# Sensors.net
KiCad netlist of a schematic drawn in Altium Designer
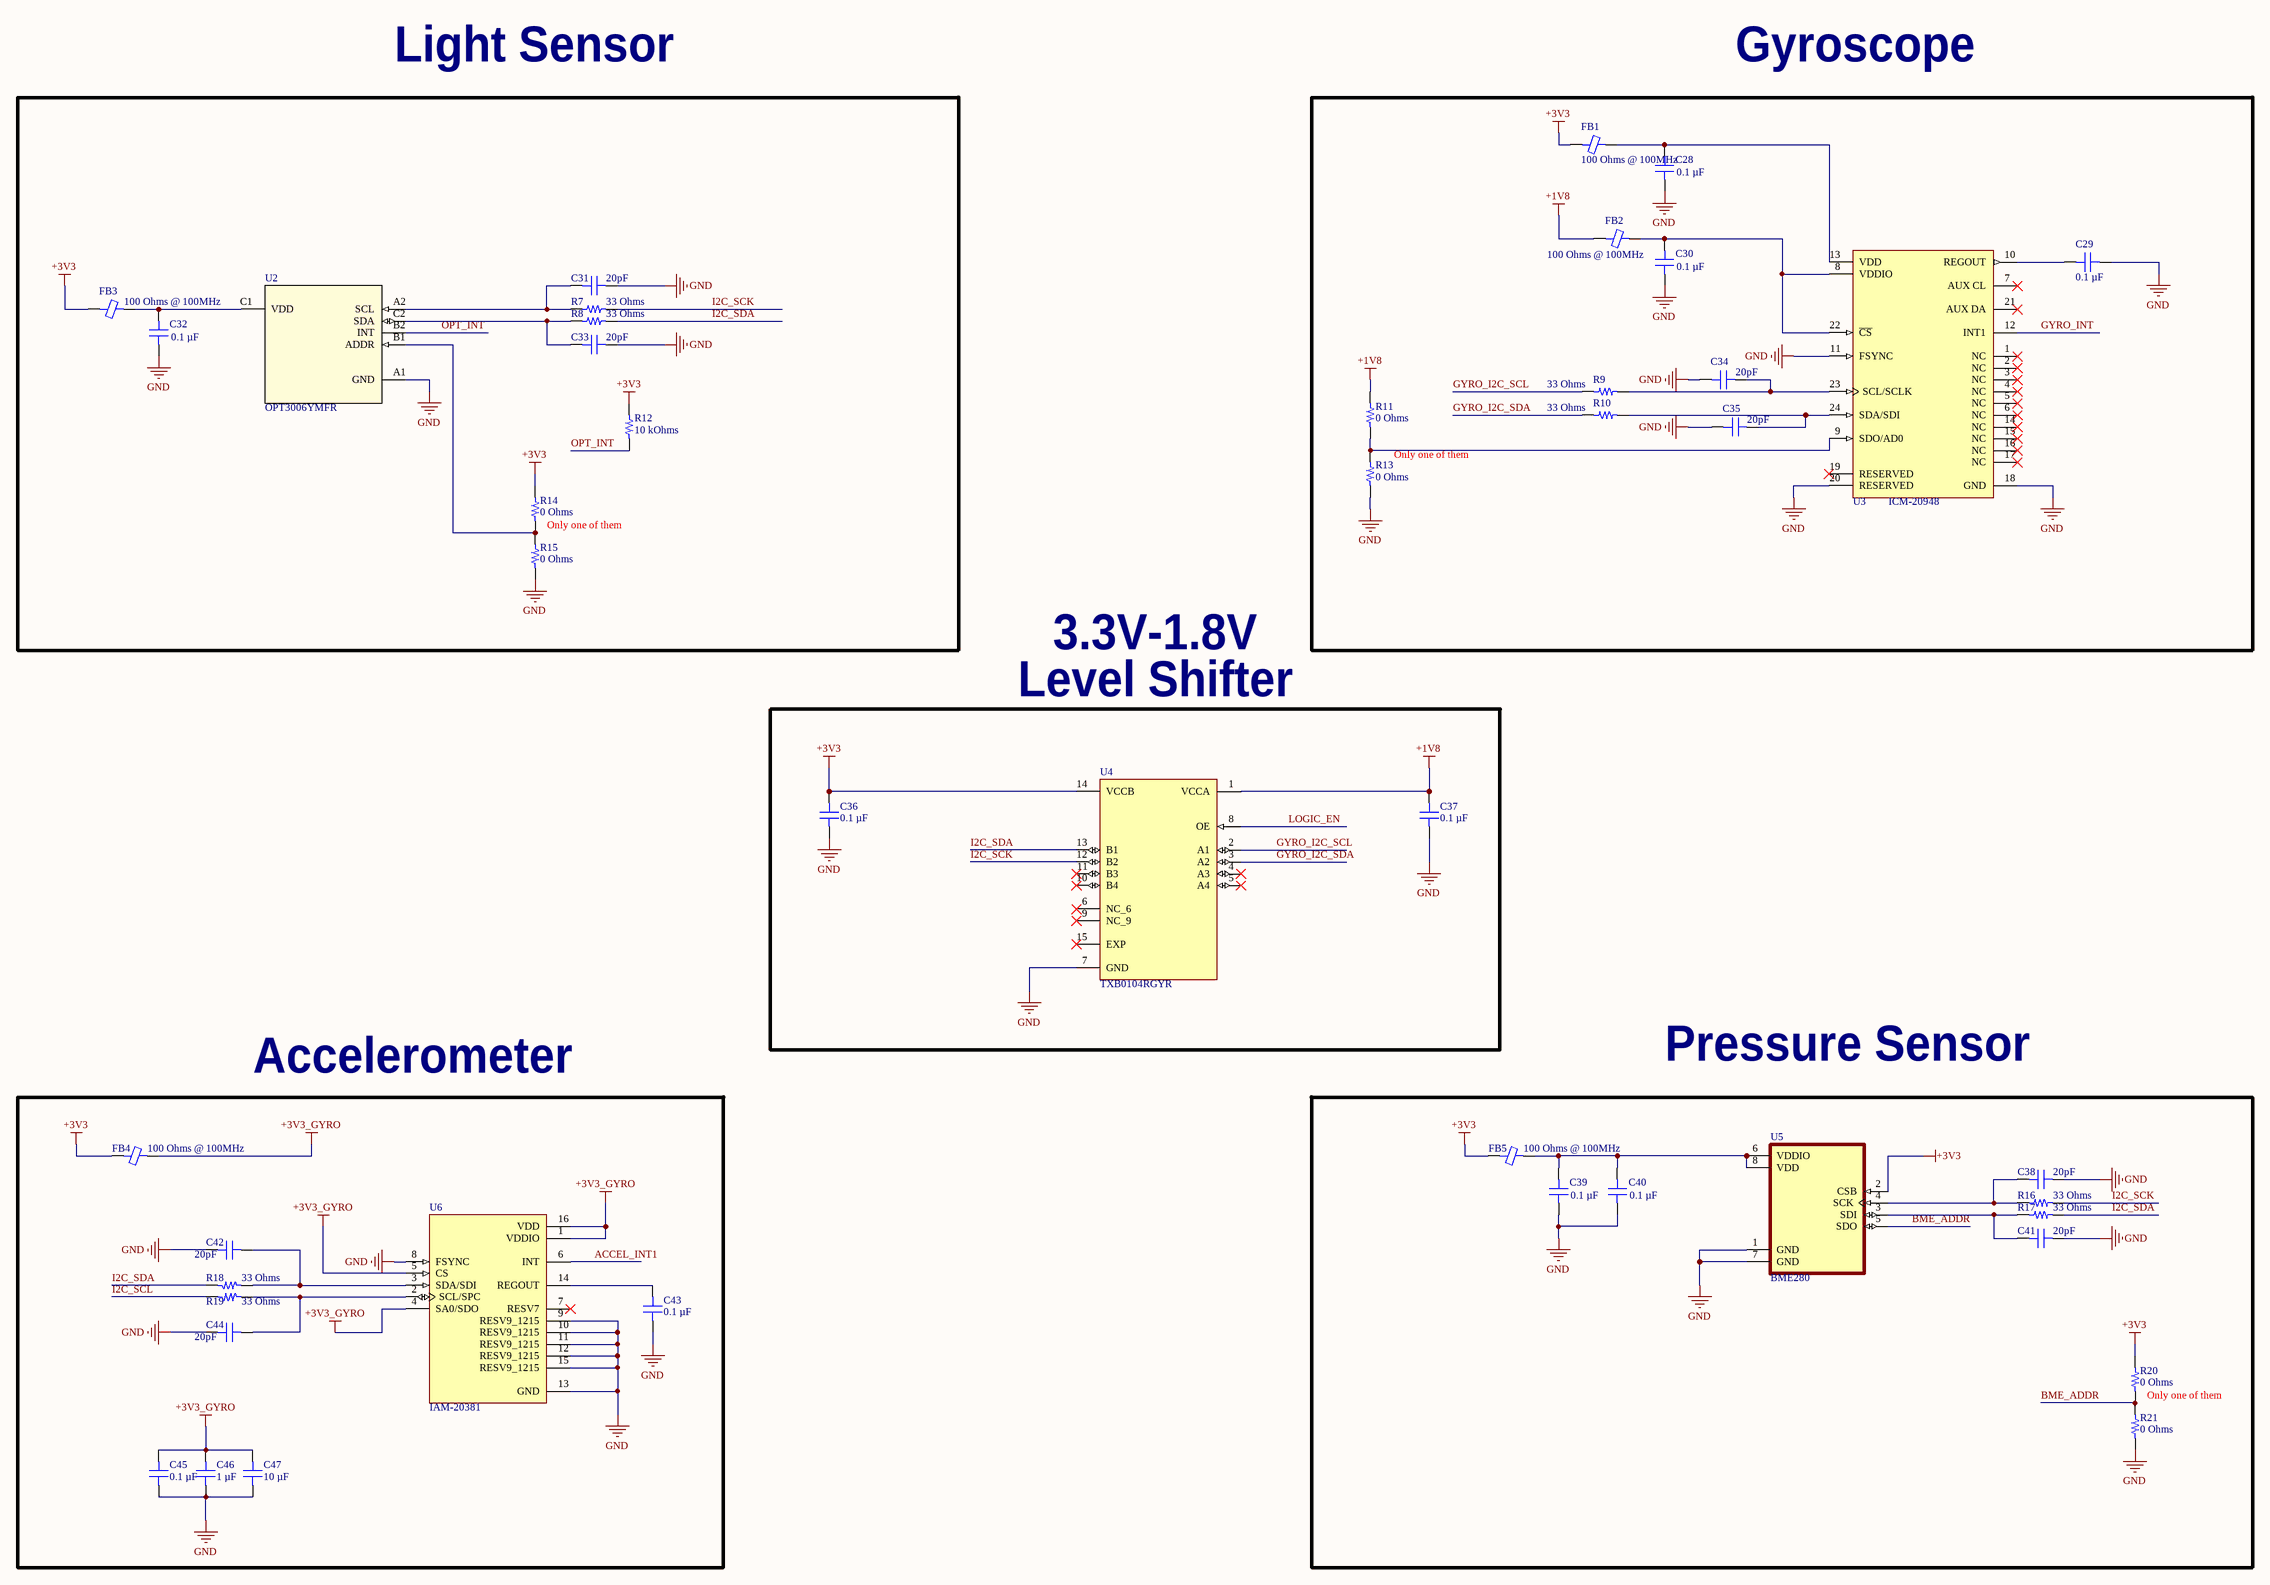
[diagram p0: Sensors.SchDoc]

(export (version "E")
  (design (tool "Eeschema 10.0.6"))
  (components
    (comp (ref "C28")
      (value "0.1 µF")
      (footprint "CAP 0603_1608")
      (description "CAP CER 0.1UF 16V X7R 0603")
      (fields (field (name "PART NUMBER") "CS0603KRX7R7BB104") (field (name "MANUFACTURER") "Yageo"))
      (libsource (lib "Celestial Altium Library - altium_library") (part "Capacitor"))
    )
    (comp (ref "C29")
      (value "0.1 µF")
      (footprint "CAP 0603_1608")
      (description "CAP CER 0.1UF 16V X7R 0603")
      (fields (field (name "PART NUMBER") "CS0603KRX7R7BB104") (field (name "MANUFACTURER") "Yageo"))
      (libsource (lib "Celestial Altium Library - altium_library") (part "Capacitor"))
    )
    (comp (ref "C30")
      (value "0.1 µF")
      (footprint "CAP 0603_1608")
      (description "CAP CER 0.1UF 16V X7R 0603")
      (fields (field (name "PART NUMBER") "CS0603KRX7R7BB104") (field (name "MANUFACTURER") "Yageo"))
      (libsource (lib "Celestial Altium Library - altium_library") (part "Capacitor"))
    )
    (comp (ref "C31")
      (value "20pF")
      (footprint "CAP 0603_1608")
      (description "CAP CER 20PF 25V C0G/NP0 0603")
      (fields (field (name "PART NUMBER") "06033A200JAT2A") (field (name "MANUFACTURER") "AVX Corporation"))
      (libsource (lib "Celestial Altium Library - altium_library") (part "Capacitor"))
    )
    (comp (ref "C32")
      (value "0.1 µF")
      (footprint "CAP 0603_1608")
      (description "CAP CER 0.1UF 16V X7R 0603")
      (fields (field (name "PART NUMBER") "CS0603KRX7R7BB104") (field (name "MANUFACTURER") "Yageo"))
      (libsource (lib "Celestial Altium Library - altium_library") (part "Capacitor"))
    )
    (comp (ref "C33")
      (value "20pF")
      (footprint "CAP 0603_1608")
      (description "CAP CER 20PF 25V C0G/NP0 0603")
      (fields (field (name "PART NUMBER") "06033A200JAT2A") (field (name "MANUFACTURER") "AVX Corporation"))
      (libsource (lib "Celestial Altium Library - altium_library") (part "Capacitor"))
    )
    (comp (ref "C34")
      (value "20pF")
      (footprint "CAP 0603_1608")
      (description "CAP CER 20PF 25V C0G/NP0 0603")
      (fields (field (name "PART NUMBER") "06033A200JAT2A") (field (name "MANUFACTURER") "AVX Corporation"))
      (libsource (lib "Celestial Altium Library - altium_library") (part "Capacitor"))
    )
    (comp (ref "C35")
      (value "20pF")
      (footprint "CAP 0603_1608")
      (description "CAP CER 20PF 25V C0G/NP0 0603")
      (fields (field (name "PART NUMBER") "06033A200JAT2A") (field (name "MANUFACTURER") "AVX Corporation"))
      (libsource (lib "Celestial Altium Library - altium_library") (part "Capacitor"))
    )
    (comp (ref "C36")
      (value "0.1 µF")
      (footprint "CAP 0603_1608")
      (description "CAP CER 0.1UF 25V X5R 0603")
      (fields (field (name "PART NUMBER") "TMK107BJ104KA-T") (field (name "MANUFACTURER") "Taiyo Yuden"))
      (libsource (lib "Celestial Altium Library - altium_library") (part "Capacitor"))
    )
    (comp (ref "C37")
      (value "0.1 µF")
      (footprint "CAP 0603_1608")
      (description "CAP CER 0.1UF 25V X5R 0603")
      (fields (field (name "PART NUMBER") "TMK107BJ104KA-T") (field (name "MANUFACTURER") "Taiyo Yuden"))
      (libsource (lib "Celestial Altium Library - altium_library") (part "Capacitor"))
    )
    (comp (ref "C38")
      (value "20pF")
      (footprint "CAP 0603_1608")
      (description "CAP CER 20PF 25V C0G/NP0 0603")
      (fields (field (name "PART NUMBER") "06033A200JAT2A") (field (name "MANUFACTURER") "AVX Corporation"))
      (libsource (lib "Celestial Altium Library - altium_library") (part "Capacitor"))
    )
    (comp (ref "C39")
      (value "0.1 µF")
      (footprint "CAP 0603_1608")
      (description "CAP CER 0.1UF 16V X7R 0603")
      (fields (field (name "PART NUMBER") "CS0603KRX7R7BB104") (field (name "MANUFACTURER") "Yageo"))
      (libsource (lib "Celestial Altium Library - altium_library") (part "Capacitor"))
    )
    (comp (ref "C40")
      (value "0.1 µF")
      (footprint "CAP 0603_1608")
      (description "CAP CER 0.1UF 16V X7R 0603")
      (fields (field (name "PART NUMBER") "CS0603KRX7R7BB104") (field (name "MANUFACTURER") "Yageo"))
      (libsource (lib "Celestial Altium Library - altium_library") (part "Capacitor"))
    )
    (comp (ref "C41")
      (value "20pF")
      (footprint "CAP 0603_1608")
      (description "CAP CER 20PF 25V C0G/NP0 0603")
      (fields (field (name "PART NUMBER") "06033A200JAT2A") (field (name "MANUFACTURER") "AVX Corporation"))
      (libsource (lib "Celestial Altium Library - altium_library") (part "Capacitor"))
    )
    (comp (ref "C42")
      (value "20pF")
      (footprint "CAP 0603_1608")
      (description "CAP CER 20PF 25V C0G/NP0 0603")
      (fields (field (name "PART NUMBER") "06033A200JAT2A") (field (name "MANUFACTURER") "AVX Corporation"))
      (libsource (lib "Celestial Altium Library - altium_library") (part "Capacitor"))
    )
    (comp (ref "C43")
      (value "0.1 µF")
      (footprint "CAP 0603_1608")
      (description "CAP CER 0.1UF 25V X5R 0603")
      (fields (field (name "PART NUMBER") "TMK107BJ104KA-T") (field (name "MANUFACTURER") "Taiyo Yuden"))
      (libsource (lib "Celestial Altium Library - altium_library") (part "Capacitor"))
    )
    (comp (ref "C44")
      (value "20pF")
      (footprint "CAP 0603_1608")
      (description "CAP CER 20PF 25V C0G/NP0 0603")
      (fields (field (name "PART NUMBER") "06033A200JAT2A") (field (name "MANUFACTURER") "AVX Corporation"))
      (libsource (lib "Celestial Altium Library - altium_library") (part "Capacitor"))
    )
    (comp (ref "C45")
      (value "0.1 µF")
      (footprint "CAP 0603_1608")
      (description "CAP CER 0.1UF 25V X5R 0603")
      (fields (field (name "PART NUMBER") "TMK107BJ104KA-T") (field (name "MANUFACTURER") "Taiyo Yuden"))
      (libsource (lib "Celestial Altium Library - altium_library") (part "Capacitor"))
    )
    (comp (ref "C46")
      (value "1 µF")
      (footprint "CAP 0603_1608")
      (description "CAP CER 1UF 25V X5R 0603")
      (fields (field (name "PART NUMBER") "TMK107BJ105MAHT") (field (name "MANUFACTURER") "Taiyo Yuden"))
      (libsource (lib "Celestial Altium Library - altium_library") (part "Capacitor"))
    )
    (comp (ref "C47")
      (value "10 µF")
      (footprint "CAP 0603_1608")
      (description "CAP CER 10UF 25V X5R 0603")
      (fields (field (name "PART NUMBER") "TMK107BBJ106MA-T") (field (name "MANUFACTURER") "Taiyo Yuden"))
      (libsource (lib "Celestial Altium Library - altium_library") (part "Capacitor"))
    )
    (comp (ref "FB1")
      (value "100 Ohms @ 100MHz")
      (footprint "FER 0402_1005")
      (description "EMI BEAD FILETER")
      (fields
        (field (name "PART NUMBER") "BBSY00100505101Y00")
        (field (name "MANUFACTURER") "Chilisin Electronics")
      )
      (libsource (lib "Celestial Altium Library - altium_library") (part "Ferrite Chip"))
    )
    (comp (ref "FB2")
      (value "100 Ohms @ 100MHz")
      (footprint "FER 0402_1005")
      (description "EMI BEAD FILETER")
      (fields
        (field (name "PART NUMBER") "BBSY00100505101Y00")
        (field (name "MANUFACTURER") "Chilisin Electronics")
      )
      (libsource (lib "Celestial Altium Library - altium_library") (part "Ferrite Chip"))
    )
    (comp (ref "FB3")
      (value "100 Ohms @ 100MHz")
      (footprint "FER 0402_1005")
      (description "EMI BEAD FILETER")
      (fields
        (field (name "PART NUMBER") "BBSY00100505101Y00")
        (field (name "MANUFACTURER") "Chilisin Electronics")
      )
      (libsource (lib "Celestial Altium Library - altium_library") (part "Ferrite Chip"))
    )
    (comp (ref "FB4")
      (value "100 Ohms @ 100MHz")
      (footprint "FER 0402_1005")
      (description "EMI BEAD FILETER")
      (fields
        (field (name "PART NUMBER") "BBSY00100505101Y00")
        (field (name "MANUFACTURER") "Chilisin Electronics")
      )
      (libsource (lib "Celestial Altium Library - altium_library") (part "Ferrite Chip"))
    )
    (comp (ref "FB5")
      (value "100 Ohms @ 100MHz")
      (footprint "FER 0402_1005")
      (description "EMI BEAD FILETER")
      (fields
        (field (name "PART NUMBER") "BBSY00100505101Y00")
        (field (name "MANUFACTURER") "Chilisin Electronics")
      )
      (libsource (lib "Celestial Altium Library - altium_library") (part "Ferrite Chip"))
    )
    (comp (ref "R7")
      (value "33 Ohms")
      (footprint "RES 0603_1608")
      (description "RES SMD 33 OHM 1% 1/10W 0603")
      (fields (field (name "PART NUMBER") "AC0603FR-0733RL") (field (name "MANUFACTURER") "Yageo"))
      (libsource (lib "Celestial Altium Library - altium_library") (part "Resistor"))
    )
    (comp (ref "R8")
      (value "33 Ohms")
      (footprint "RES 0603_1608")
      (description "RES SMD 33 OHM 1% 1/10W 0603")
      (fields (field (name "PART NUMBER") "AC0603FR-0733RL") (field (name "MANUFACTURER") "Yageo"))
      (libsource (lib "Celestial Altium Library - altium_library") (part "Resistor"))
    )
    (comp (ref "R9")
      (value "33 Ohms")
      (footprint "RES 0603_1608")
      (description "RES SMD 33 OHM 1% 1/10W 0603")
      (fields (field (name "PART NUMBER") "AC0603FR-0733RL") (field (name "MANUFACTURER") "Yageo"))
      (libsource (lib "Celestial Altium Library - altium_library") (part "Resistor"))
    )
    (comp (ref "R10")
      (value "33 Ohms")
      (footprint "RES 0603_1608")
      (description "RES SMD 33 OHM 1% 1/10W 0603")
      (fields (field (name "PART NUMBER") "AC0603FR-0733RL") (field (name "MANUFACTURER") "Yageo"))
      (libsource (lib "Celestial Altium Library - altium_library") (part "Resistor"))
    )
    (comp (ref "R11")
      (value "0 Ohms")
      (footprint "RES 0603_1608")
      (description "RES SMD 0 OHM JUMPER 1/2W 0603")
      (fields (field (name "PART NUMBER") "5110") (field (name "MANUFACTURER") "Keystone Electronics"))
      (libsource (lib "Celestial Altium Library - altium_library") (part "Resistor"))
    )
    (comp (ref "R12")
      (value "10 kOhms")
      (footprint "RES 0603_1608")
      (description "RES SMD 10K OHM 5% 1/10W 0603")
      (fields (field (name "PART NUMBER") "AC0603JR-0710KL") (field (name "MANUFACTURER") "Yageo"))
      (libsource (lib "Celestial Altium Library - altium_library") (part "Resistor"))
    )
    (comp (ref "R13")
      (value "0 Ohms")
      (footprint "RES 0603_1608")
      (description "RES SMD 0 OHM JUMPER 1/2W 0603")
      (fields (field (name "PART NUMBER") "5110") (field (name "MANUFACTURER") "Keystone Electronics"))
      (libsource (lib "Celestial Altium Library - altium_library") (part "Resistor"))
    )
    (comp (ref "R14")
      (value "0 Ohms")
      (footprint "RES 0603_1608")
      (description "RES SMD 0 OHM JUMPER 1/2W 0603")
      (fields (field (name "PART NUMBER") "5110") (field (name "MANUFACTURER") "Keystone Electronics"))
      (libsource (lib "Celestial Altium Library - altium_library") (part "Resistor"))
    )
    (comp (ref "R15")
      (value "0 Ohms")
      (footprint "RES 0603_1608")
      (description "RES SMD 0 OHM JUMPER 1/2W 0603")
      (fields (field (name "PART NUMBER") "5110") (field (name "MANUFACTURER") "Keystone Electronics"))
      (libsource (lib "Celestial Altium Library - altium_library") (part "Resistor"))
    )
    (comp (ref "R16")
      (value "33 Ohms")
      (footprint "RES 0603_1608")
      (description "RES SMD 33 OHM 1% 1/10W 0603")
      (fields (field (name "PART NUMBER") "AC0603FR-0733RL") (field (name "MANUFACTURER") "Yageo"))
      (libsource (lib "Celestial Altium Library - altium_library") (part "Resistor"))
    )
    (comp (ref "R17")
      (value "33 Ohms")
      (footprint "RES 0603_1608")
      (description "RES SMD 33 OHM 1% 1/10W 0603")
      (fields (field (name "PART NUMBER") "AC0603FR-0733RL") (field (name "MANUFACTURER") "Yageo"))
      (libsource (lib "Celestial Altium Library - altium_library") (part "Resistor"))
    )
    (comp (ref "R18")
      (value "33 Ohms")
      (footprint "RES 0603_1608")
      (description "RES SMD 33 OHM 1% 1/10W 0603")
      (fields (field (name "PART NUMBER") "AC0603FR-0733RL") (field (name "MANUFACTURER") "Yageo"))
      (libsource (lib "Celestial Altium Library - altium_library") (part "Resistor"))
    )
    (comp (ref "R19")
      (value "33 Ohms")
      (footprint "RES 0603_1608")
      (description "RES SMD 33 OHM 1% 1/10W 0603")
      (fields (field (name "PART NUMBER") "AC0603FR-0733RL") (field (name "MANUFACTURER") "Yageo"))
      (libsource (lib "Celestial Altium Library - altium_library") (part "Resistor"))
    )
    (comp (ref "R20")
      (value "0 Ohms")
      (footprint "RES 0603_1608")
      (description "RES SMD 0 OHM JUMPER 1/2W 0603")
      (fields (field (name "PART NUMBER") "5110") (field (name "MANUFACTURER") "Keystone Electronics"))
      (libsource (lib "Celestial Altium Library - altium_library") (part "Resistor"))
    )
    (comp (ref "R21")
      (value "0 Ohms")
      (footprint "RES 0603_1608")
      (description "RES SMD 0 OHM JUMPER 1/2W 0603")
      (fields (field (name "PART NUMBER") "5110") (field (name "MANUFACTURER") "Keystone Electronics"))
      (libsource (lib "Celestial Altium Library - altium_library") (part "Resistor"))
    )
    (comp (ref "U2")
      (value "OPT3006YMFR")
      (footprint "YMF0006A")
      (description "No Description Available")
      (fields (field (name "COPYRIGHT") "Copyright (C) 2022 Ultra Librarian. All rights reserved."))
      (libsource (lib "OPT3006YMFR") (part "OPT3006YMFR"))
    )
    (comp (ref "U3")
      (value "ICM-20948")
      (footprint "TDK_InvenSense_0_IPC_C")
      (description "Accelerometer, Gyroscope, Magnetometer, 9 Axis Sensor I²C, SPI Output")
      (fields
        (field (name "DIGIKEY PART NUMBER") "1428-1123-1-ND")
        (field (name "MANUFACTURER") "TDK InvenSense")
      )
      (libsource (lib "EEConcierge") (part "ICM-20948"))
    )
    (comp (ref "U4")
      (value "TXB0104RGYR")
      (footprint "QFN50P350X350X100-15N")
      (libsource (lib "TXB0104RGYR") (part "TXB0104RGYR"))
    )
    (comp (ref "U5")
      (value "BME280")
      (footprint "PSON65P250X250X100-8N")
      (libsource (lib "BME280") (part "BME280"))
    )
    (comp (ref "U6")
      (value "IAM-20381")
      (footprint "PQFN50P300X300X80-16N")
      (description "Accelerometer X, Y, Z Axis Â±2g, 4g, 8g, 16g 16-LGA (3x3)")
      (fields (field (name "MF") "TDK InvenSense"))
      (libsource (lib "IAM-20381") (part "IAM-20381"))
    )
  )
  (nets
    (net (code "1") (name "+1V8") (class "Default")
      (node (ref "C37") (pin "2") (pinfunction "2_2") (pintype "passive"))
      (node (ref "FB2") (pin "1") (pinfunction "1_1") (pintype "passive"))
      (node (ref "R11") (pin "2") (pinfunction "2_2") (pintype "passive"))
      (node (ref "U4") (pin "1") (pinfunction "VCCA_1") (pintype "power_in"))
    )
    (net (code "2") (name "+3V3") (class "Default")
      (node (ref "C36") (pin "2") (pinfunction "2_2") (pintype "passive"))
      (node (ref "FB1") (pin "1") (pinfunction "1_1") (pintype "passive"))
      (node (ref "FB3") (pin "1") (pinfunction "1_1") (pintype "passive"))
      (node (ref "FB4") (pin "1") (pinfunction "1_1") (pintype "passive"))
      (node (ref "FB5") (pin "1") (pinfunction "1_1") (pintype "passive"))
      (node (ref "R12") (pin "1") (pinfunction "1_1") (pintype "passive"))
      (node (ref "R14") (pin "2") (pinfunction "2_2") (pintype "passive"))
      (node (ref "R20") (pin "2") (pinfunction "2_2") (pintype "passive"))
      (node (ref "U4") (pin "14") (pinfunction "VCCB_14") (pintype "power_in"))
      (node (ref "U5") (pin "2") (pinfunction "CSB_2") (pintype "input"))
    )
    (net (code "3") (name "+3V3_GYRO") (class "Default")
      (node (ref "C45") (pin "2") (pinfunction "2_2") (pintype "passive"))
      (node (ref "C46") (pin "2") (pinfunction "2_2") (pintype "passive"))
      (node (ref "C47") (pin "2") (pinfunction "2_2") (pintype "passive"))
      (node (ref "FB4") (pin "2") (pinfunction "2_2") (pintype "passive"))
      (node (ref "U6") (pin "1") (pinfunction "VDDIO_1") (pintype "power_in"))
      (node (ref "U6") (pin "16") (pinfunction "VDD_16") (pintype "power_in"))
      (node (ref "U6") (pin "4") (pinfunction "SA0/SDO_4") (pintype "power_in"))
      (node (ref "U6") (pin "5") (pinfunction "CS_5") (pintype "input"))
    )
    (net (code "4") (name "/ACCEL_INT1") (class "Default")
      (node (ref "U6") (pin "6") (pinfunction "INT_6") (pintype "passive"))
    )
    (net (code "5") (name "/BME_ADDR") (class "Default")
      (node (ref "R20") (pin "1") (pinfunction "1_1") (pintype "passive"))
      (node (ref "R21") (pin "2") (pinfunction "2_2") (pintype "passive"))
      (node (ref "U5") (pin "5") (pinfunction "SDO_5") (pintype "bidirectional"))
    )
    (net (code "6") (name "/GYRO_I2C_SCL") (class "Default")
      (node (ref "R9") (pin "1") (pinfunction "1_1") (pintype "passive"))
      (node (ref "U4") (pin "2") (pinfunction "A1_2") (pintype "bidirectional"))
    )
    (net (code "7") (name "/GYRO_I2C_SDA") (class "Default")
      (node (ref "R10") (pin "1") (pinfunction "1_1") (pintype "passive"))
      (node (ref "U4") (pin "3") (pinfunction "A2_3") (pintype "bidirectional"))
    )
    (net (code "8") (name "/GYRO_INT") (class "Default")
      (node (ref "U3") (pin "12") (pinfunction "INT1_12") (pintype "passive"))
    )
    (net (code "9") (name "/I2C_SCK") (class "Default")
      (node (ref "R16") (pin "2") (pinfunction "2_2") (pintype "passive"))
      (node (ref "R7") (pin "2") (pinfunction "2_2") (pintype "passive"))
      (node (ref "U4") (pin "12") (pinfunction "B2_12") (pintype "bidirectional"))
    )
    (net (code "10") (name "/I2C_SCL") (class "Default")
      (node (ref "R19") (pin "2") (pinfunction "2_2") (pintype "passive"))
    )
    (net (code "11") (name "/I2C_SDA") (class "Default")
      (node (ref "R17") (pin "2") (pinfunction "2_2") (pintype "passive"))
      (node (ref "R18") (pin "2") (pinfunction "2_2") (pintype "passive"))
      (node (ref "R8") (pin "2") (pinfunction "2_2") (pintype "passive"))
      (node (ref "U4") (pin "13") (pinfunction "B1_13") (pintype "bidirectional"))
    )
    (net (code "12") (name "/LOGIC_EN") (class "Default")
      (node (ref "U4") (pin "8") (pinfunction "OE_8") (pintype "input"))
    )
    (net (code "13") (name "/OPT_INT") (class "Default")
      (node (ref "R12") (pin "2") (pinfunction "2_2") (pintype "passive"))
      (node (ref "U2") (pin "B2") (pinfunction "INT_B2") (pintype "passive"))
    )
    (net (code "14") (name "GND") (class "Default")
      (node (ref "C28") (pin "1") (pinfunction "1_1") (pintype "passive"))
      (node (ref "C29") (pin "1") (pinfunction "1_1") (pintype "passive"))
      (node (ref "C30") (pin "1") (pinfunction "1_1") (pintype "passive"))
      (node (ref "C31") (pin "2") (pinfunction "2_2") (pintype "passive"))
      (node (ref "C32") (pin "1") (pinfunction "1_1") (pintype "passive"))
      (node (ref "C33") (pin "2") (pinfunction "2_2") (pintype "passive"))
      (node (ref "C34") (pin "1") (pinfunction "1_1") (pintype "passive"))
      (node (ref "C35") (pin "1") (pinfunction "1_1") (pintype "passive"))
      (node (ref "C36") (pin "1") (pinfunction "1_1") (pintype "passive"))
      (node (ref "C37") (pin "1") (pinfunction "1_1") (pintype "passive"))
      (node (ref "C38") (pin "2") (pinfunction "2_2") (pintype "passive"))
      (node (ref "C39") (pin "1") (pinfunction "1_1") (pintype "passive"))
      (node (ref "C40") (pin "1") (pinfunction "1_1") (pintype "passive"))
      (node (ref "C41") (pin "2") (pinfunction "2_2") (pintype "passive"))
      (node (ref "C42") (pin "2") (pinfunction "2_2") (pintype "passive"))
      (node (ref "C43") (pin "1") (pinfunction "1_1") (pintype "passive"))
      (node (ref "C44") (pin "2") (pinfunction "2_2") (pintype "passive"))
      (node (ref "C45") (pin "1") (pinfunction "1_1") (pintype "passive"))
      (node (ref "C46") (pin "1") (pinfunction "1_1") (pintype "passive"))
      (node (ref "C47") (pin "1") (pinfunction "1_1") (pintype "passive"))
      (node (ref "R13") (pin "1") (pinfunction "1_1") (pintype "passive"))
      (node (ref "R15") (pin "1") (pinfunction "1_1") (pintype "passive"))
      (node (ref "R21") (pin "1") (pinfunction "1_1") (pintype "passive"))
      (node (ref "U2") (pin "A1") (pinfunction "GND_A1") (pintype "power_in"))
      (node (ref "U3") (pin "11") (pinfunction "FSYNC_11") (pintype "input"))
      (node (ref "U3") (pin "18") (pinfunction "GND_18") (pintype "power_in"))
      (node (ref "U3") (pin "20") (pinfunction "RESERVED_20") (pintype "passive"))
      (node (ref "U4") (pin "7") (pinfunction "GND_7") (pintype "power_in"))
      (node (ref "U5") (pin "1") (pinfunction "GND_1") (pintype "power_in"))
      (node (ref "U5") (pin "7") (pinfunction "GND_7") (pintype "power_in"))
      (node (ref "U6") (pin "10") (pinfunction "RESV9_1215_10") (pintype "passive"))
      (node (ref "U6") (pin "11") (pinfunction "RESV9_1215_11") (pintype "passive"))
      (node (ref "U6") (pin "12") (pinfunction "RESV9_1215_12") (pintype "passive"))
      (node (ref "U6") (pin "13") (pinfunction "GND_13") (pintype "power_in"))
      (node (ref "U6") (pin "15") (pinfunction "RESV9_1215_15") (pintype "passive"))
      (node (ref "U6") (pin "8") (pinfunction "FSYNC_8") (pintype "input"))
      (node (ref "U6") (pin "9") (pinfunction "RESV9_1215_9") (pintype "passive"))
    )
    (net (code "15") (name "Net-(U2-ADDR)") (class "Default")
      (node (ref "R14") (pin "1") (pinfunction "1_1") (pintype "passive"))
      (node (ref "R15") (pin "2") (pinfunction "2_2") (pintype "passive"))
      (node (ref "U2") (pin "B1") (pinfunction "ADDR_B1") (pintype "input"))
    )
    (net (code "16") (name "Net-(U2-SCL)") (class "Default")
      (node (ref "C31") (pin "1") (pinfunction "1_1") (pintype "passive"))
      (node (ref "R7") (pin "1") (pinfunction "1_1") (pintype "passive"))
      (node (ref "U2") (pin "A2") (pinfunction "SCL_A2") (pintype "input"))
    )
    (net (code "17") (name "Net-(U2-SDA)") (class "Default")
      (node (ref "C33") (pin "1") (pinfunction "1_1") (pintype "passive"))
      (node (ref "R8") (pin "1") (pinfunction "1_1") (pintype "passive"))
      (node (ref "U2") (pin "C2") (pinfunction "SDA_C2") (pintype "bidirectional"))
    )
    (net (code "18") (name "Net-(U2-VDD)") (class "Default")
      (node (ref "C32") (pin "2") (pinfunction "2_2") (pintype "passive"))
      (node (ref "FB3") (pin "2") (pinfunction "2_2") (pintype "passive"))
      (node (ref "U2") (pin "C1") (pinfunction "VDD_C1") (pintype "power_in"))
    )
    (net (code "19") (name "Net-(U3-REGOUT)") (class "Default")
      (node (ref "C29") (pin "2") (pinfunction "2_2") (pintype "passive"))
      (node (ref "U3") (pin "10") (pinfunction "REGOUT_10") (pintype "output"))
    )
    (net (code "20") (name "Net-(U3-SCL{slash}SCLK)") (class "Default")
      (node (ref "C34") (pin "2") (pinfunction "2_2") (pintype "passive"))
      (node (ref "R9") (pin "2") (pinfunction "2_2") (pintype "passive"))
      (node (ref "U3") (pin "23") (pinfunction "SCL/SCLK_23") (pintype "input"))
    )
    (net (code "21") (name "Net-(U3-SDA{slash}SDI)") (class "Default")
      (node (ref "C35") (pin "2") (pinfunction "2_2") (pintype "passive"))
      (node (ref "R10") (pin "2") (pinfunction "2_2") (pintype "passive"))
      (node (ref "U3") (pin "24") (pinfunction "SDA/SDI_24") (pintype "input"))
    )
    (net (code "22") (name "Net-(U3-SDO{slash}AD0)") (class "Default")
      (node (ref "R11") (pin "1") (pinfunction "1_1") (pintype "passive"))
      (node (ref "R13") (pin "2") (pinfunction "2_2") (pintype "passive"))
      (node (ref "U3") (pin "9") (pinfunction "SDO/AD0_9") (pintype "input"))
    )
    (net (code "23") (name "Net-(U3-VDD)") (class "Default")
      (node (ref "C28") (pin "2") (pinfunction "2_2") (pintype "passive"))
      (node (ref "FB1") (pin "2") (pinfunction "2_2") (pintype "passive"))
      (node (ref "U3") (pin "13") (pinfunction "VDD_13") (pintype "power_in"))
    )
    (net (code "24") (name "Net-(U3-VDDIO)") (class "Default")
      (node (ref "C30") (pin "2") (pinfunction "2_2") (pintype "passive"))
      (node (ref "FB2") (pin "2") (pinfunction "2_2") (pintype "passive"))
      (node (ref "U3") (pin "22") (pinfunction "~{CS}_22") (pintype "input"))
      (node (ref "U3") (pin "8") (pinfunction "VDDIO_8") (pintype "power_in"))
    )
    (net (code "25") (name "Net-(U5-SCK)") (class "Default")
      (node (ref "C38") (pin "1") (pinfunction "1_1") (pintype "passive"))
      (node (ref "R16") (pin "1") (pinfunction "1_1") (pintype "passive"))
      (node (ref "U5") (pin "4") (pinfunction "SCK_4") (pintype "input"))
    )
    (net (code "26") (name "Net-(U5-SDI)") (class "Default")
      (node (ref "C41") (pin "1") (pinfunction "1_1") (pintype "passive"))
      (node (ref "R17") (pin "1") (pinfunction "1_1") (pintype "passive"))
      (node (ref "U5") (pin "3") (pinfunction "SDI_3") (pintype "bidirectional"))
    )
    (net (code "27") (name "Net-(U5-VDD)") (class "Default")
      (node (ref "C39") (pin "2") (pinfunction "2_2") (pintype "passive"))
      (node (ref "C40") (pin "2") (pinfunction "2_2") (pintype "passive"))
      (node (ref "FB5") (pin "2") (pinfunction "2_2") (pintype "passive"))
      (node (ref "U5") (pin "6") (pinfunction "VDDIO_6") (pintype "power_in"))
      (node (ref "U5") (pin "8") (pinfunction "VDD_8") (pintype "power_in"))
    )
    (net (code "28") (name "Net-(U6-REGOUT)") (class "Default")
      (node (ref "C43") (pin "2") (pinfunction "2_2") (pintype "passive"))
      (node (ref "U6") (pin "14") (pinfunction "REGOUT_14") (pintype "passive"))
    )
    (net (code "29") (name "Net-(U6-SCL{slash}SPC)") (class "Default")
      (node (ref "C44") (pin "1") (pinfunction "1_1") (pintype "passive"))
      (node (ref "R19") (pin "1") (pinfunction "1_1") (pintype "passive"))
      (node (ref "U6") (pin "2") (pinfunction "SCL/SPC_2") (pintype "bidirectional"))
    )
    (net (code "30") (name "Net-(U6-SDA{slash}SDI)") (class "Default")
      (node (ref "C42") (pin "1") (pinfunction "1_1") (pintype "passive"))
      (node (ref "R18") (pin "1") (pinfunction "1_1") (pintype "passive"))
      (node (ref "U6") (pin "3") (pinfunction "SDA/SDI_3") (pintype "input"))
    )
    (net (code "31") (name "unconnected-(U3-AUX_CL-Pad7)") (class "Default")
      (node (ref "U3") (pin "7") (pinfunction "AUX_CL_7") (pintype "passive+no_connect"))
    )
    (net (code "32") (name "unconnected-(U3-AUX_DA-Pad21)") (class "Default")
      (node (ref "U3") (pin "21") (pinfunction "AUX_DA_21") (pintype "passive+no_connect"))
    )
    (net (code "33") (name "unconnected-(U3-NC-Pad1)") (class "Default")
      (node (ref "U3") (pin "1") (pinfunction "NC_1") (pintype "passive+no_connect"))
    )
    (net (code "34") (name "unconnected-(U3-NC-Pad2)") (class "Default")
      (node (ref "U3") (pin "2") (pinfunction "NC_2") (pintype "passive+no_connect"))
    )
    (net (code "35") (name "unconnected-(U3-NC-Pad3)") (class "Default")
      (node (ref "U3") (pin "3") (pinfunction "NC_3") (pintype "passive+no_connect"))
    )
    (net (code "36") (name "unconnected-(U3-NC-Pad4)") (class "Default")
      (node (ref "U3") (pin "4") (pinfunction "NC_4") (pintype "passive+no_connect"))
    )
    (net (code "37") (name "unconnected-(U3-NC-Pad5)") (class "Default")
      (node (ref "U3") (pin "5") (pinfunction "NC_5") (pintype "passive+no_connect"))
    )
    (net (code "38") (name "unconnected-(U3-NC-Pad6)") (class "Default")
      (node (ref "U3") (pin "6") (pinfunction "NC_6") (pintype "passive+no_connect"))
    )
    (net (code "39") (name "unconnected-(U3-NC-Pad14)") (class "Default")
      (node (ref "U3") (pin "14") (pinfunction "NC_14") (pintype "passive+no_connect"))
    )
    (net (code "40") (name "unconnected-(U3-NC-Pad15)") (class "Default")
      (node (ref "U3") (pin "15") (pinfunction "NC_15") (pintype "passive+no_connect"))
    )
    (net (code "41") (name "unconnected-(U3-NC-Pad16)") (class "Default")
      (node (ref "U3") (pin "16") (pinfunction "NC_16") (pintype "passive+no_connect"))
    )
    (net (code "42") (name "unconnected-(U3-NC-Pad17)") (class "Default")
      (node (ref "U3") (pin "17") (pinfunction "NC_17") (pintype "passive+no_connect"))
    )
    (net (code "43") (name "unconnected-(U3-RESERVED-Pad19)") (class "Default")
      (node (ref "U3") (pin "19") (pinfunction "RESERVED_19") (pintype "passive+no_connect"))
    )
    (net (code "44") (name "unconnected-(U4-A3-Pad4)") (class "Default")
      (node (ref "U4") (pin "4") (pinfunction "A3_4") (pintype "bidirectional+no_connect"))
    )
    (net (code "45") (name "unconnected-(U4-A4-Pad5)") (class "Default")
      (node (ref "U4") (pin "5") (pinfunction "A4_5") (pintype "bidirectional+no_connect"))
    )
    (net (code "46") (name "unconnected-(U4-B3-Pad11)") (class "Default")
      (node (ref "U4") (pin "11") (pinfunction "B3_11") (pintype "bidirectional+no_connect"))
    )
    (net (code "47") (name "unconnected-(U4-B4-Pad10)") (class "Default")
      (node (ref "U4") (pin "10") (pinfunction "B4_10") (pintype "bidirectional+no_connect"))
    )
    (net (code "48") (name "unconnected-(U4-EXP-Pad15)") (class "Default")
      (node (ref "U4") (pin "15") (pinfunction "EXP_15") (pintype "passive+no_connect"))
    )
    (net (code "49") (name "unconnected-(U4-NC_6-Pad6)") (class "Default")
      (node (ref "U4") (pin "6") (pinfunction "NC_6_6") (pintype "passive+no_connect"))
    )
    (net (code "50") (name "unconnected-(U4-NC_9-Pad9)") (class "Default")
      (node (ref "U4") (pin "9") (pinfunction "NC_9_9") (pintype "passive+no_connect"))
    )
    (net (code "51") (name "unconnected-(U6-RESV7-Pad7)") (class "Default")
      (node (ref "U6") (pin "7") (pinfunction "RESV7_7") (pintype "passive+no_connect"))
    )
  )
)
